# SCH_NFC-TAG-WITH-LED_2024-06-19.net
KiCad netlist of a schematic drawn in EasyEDA
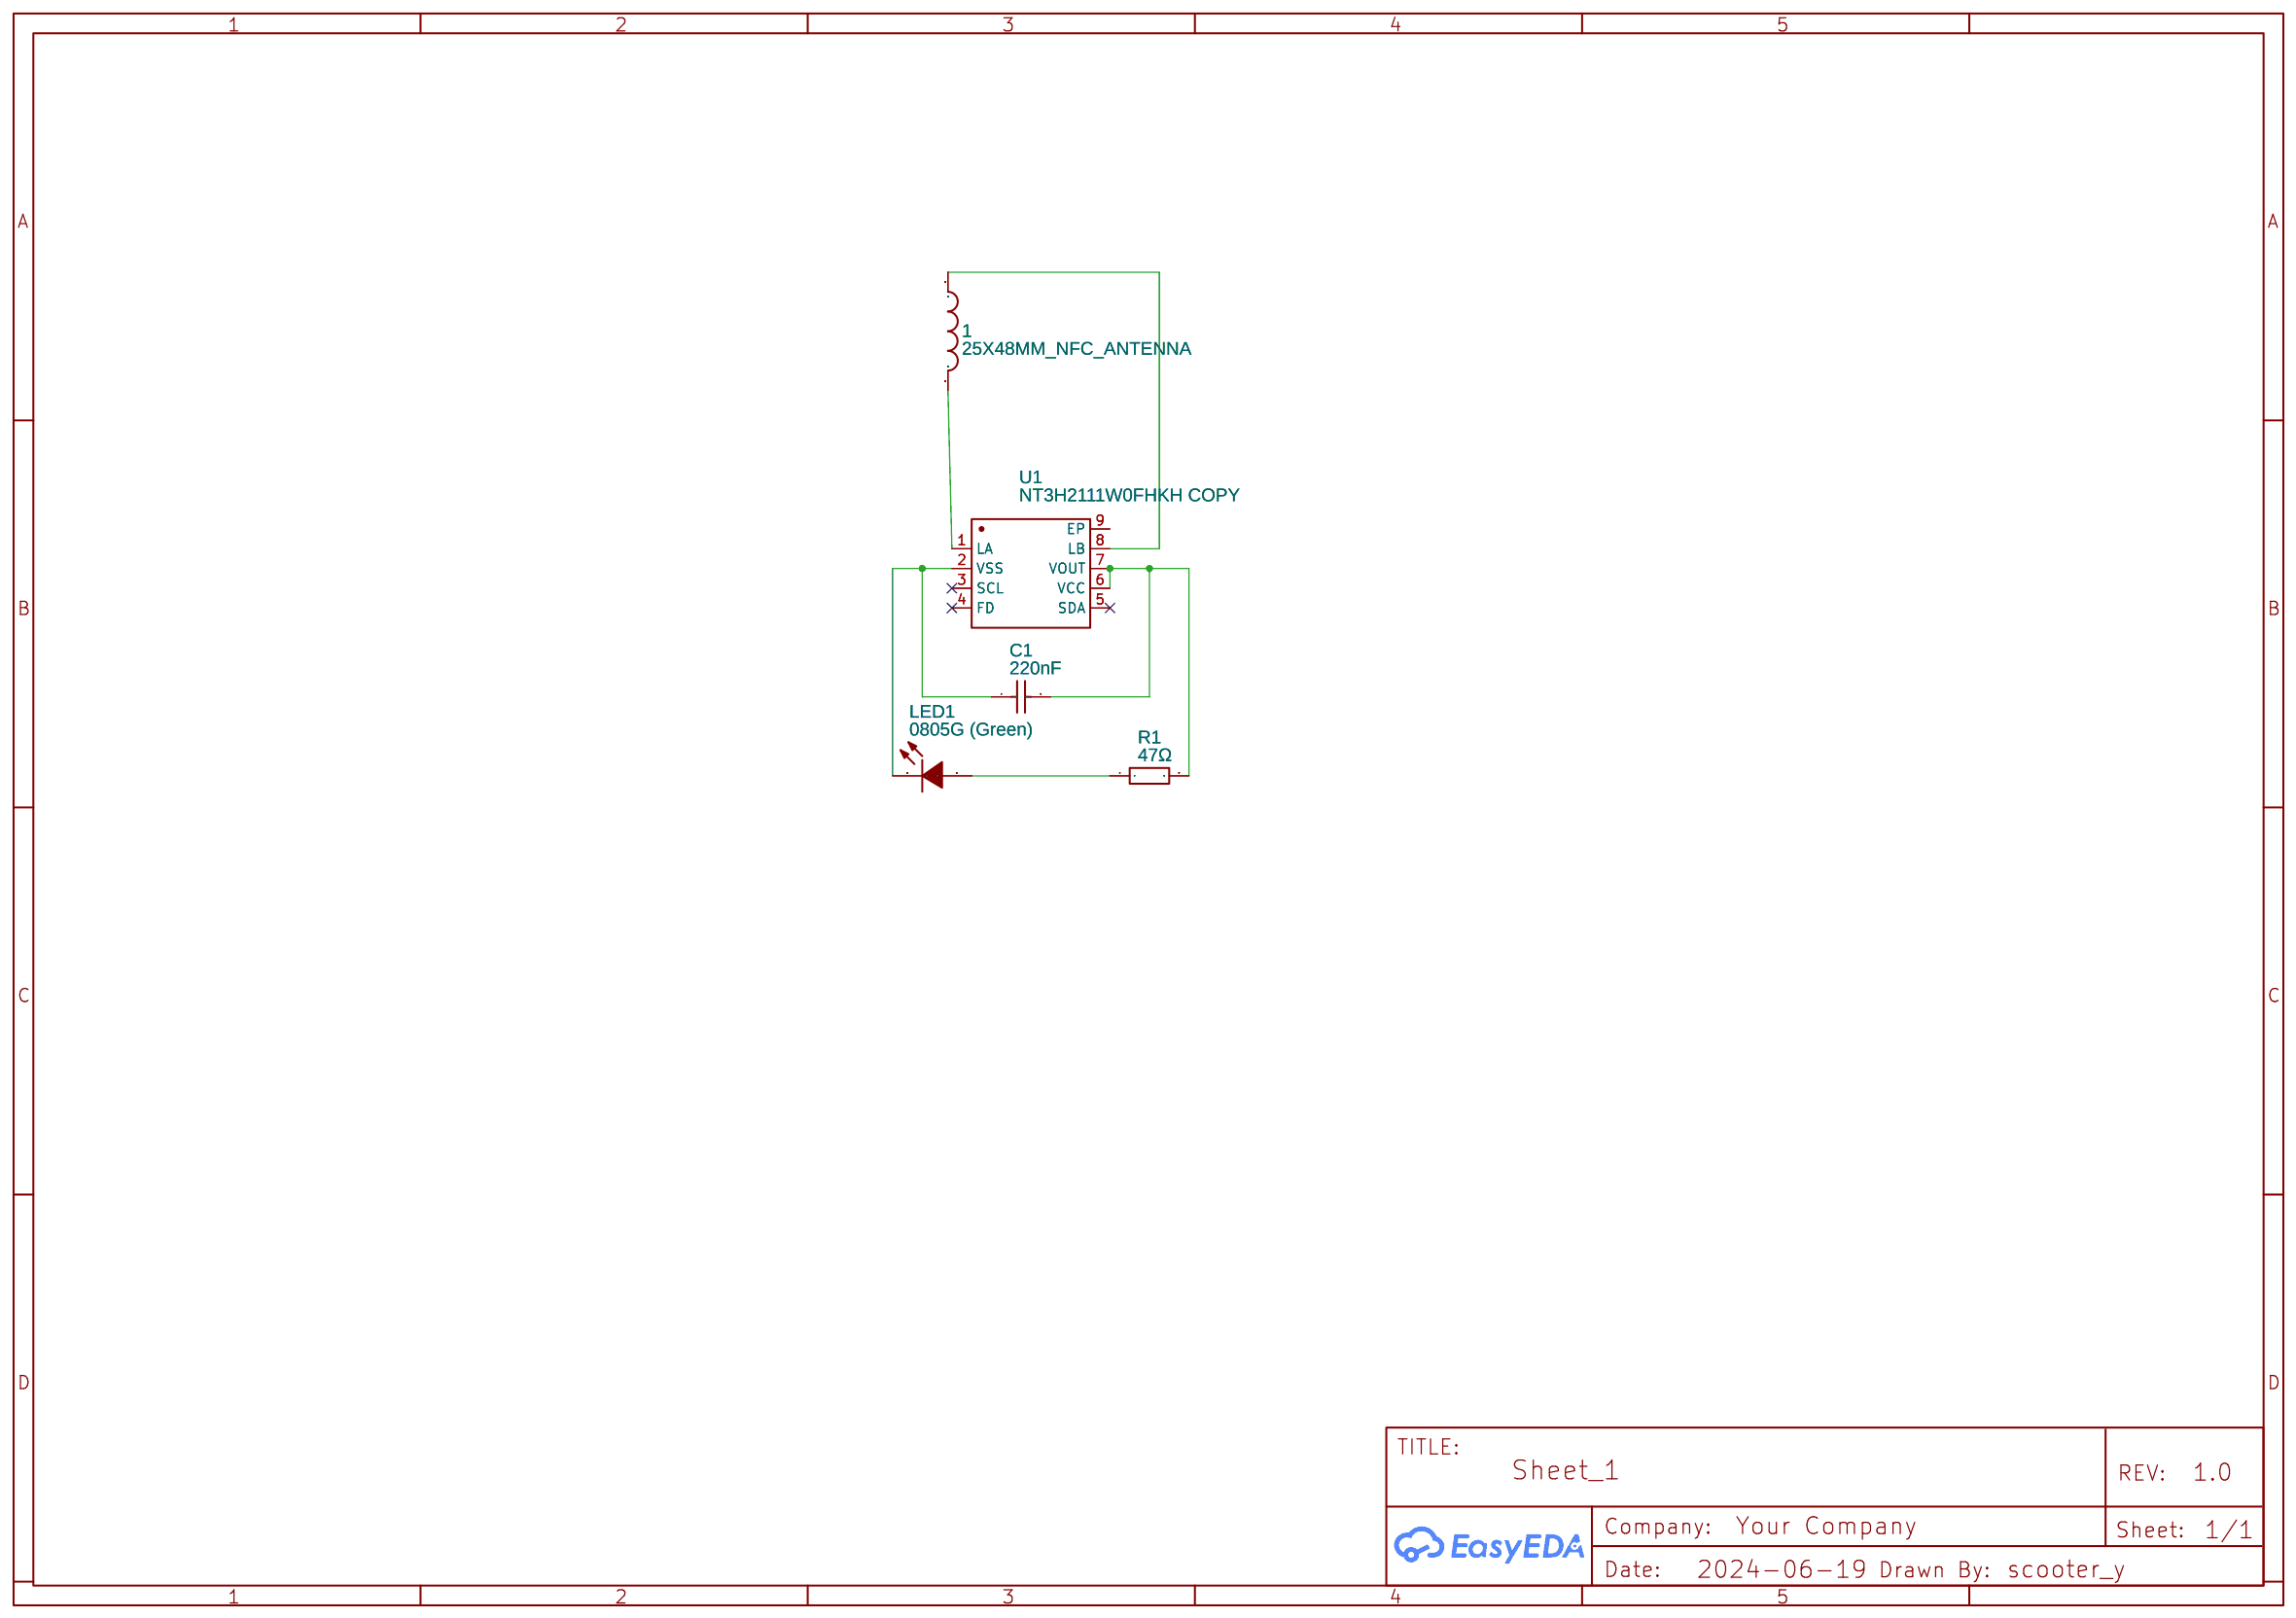
[diagram p0: schematic sheet]

(export (version "E")
  (design (tool "Eeschema 10.0.6"))
  (components
    (comp (ref "1") (value "25X48MM_NFC_ANTENNA") (libsource (lib "") (part "25X48MM_NFC_ANTENNA")))
    (comp (ref "C1")
      (value "220nF")
      (fields
        (field (name "Manufacturer Part") "CL10B224KA8NNNC")
        (field (name "Manufacturer") "SAMSUNG(三星)")
      )
      (libsource (lib "") (part "CL10B224KA8NNNC"))
    )
    (comp (ref "LED1")
      (value "0805G (Green)")
      (fields (field (name "Manufacturer Part") "KT-0805G") (field (name "Manufacturer") "KENTO"))
      (libsource (lib "") (part "0805G (Green)"))
    )
    (comp (ref "R1")
      (value "47Ω")
      (fields
        (field (name "Manufacturer Part") "0603WAF470JT5E")
        (field (name "Manufacturer") "UNI-ROYAL(厚声)")
      )
      (libsource (lib "") (part "0603WAF470JT5E"))
    )
    (comp (ref "U1")
      (value "NT3H2111W0FHKH COPY")
      (fields (field (name "Manufacturer Part") "NT3H2111W0FHKH") (field (name "Manufacturer") "NXP(恩智浦)"))
      (libsource (lib "") (part "NT3H2111W0FHKH COPY"))
    )
  )
  (nets
    (net (code "1") (name "Net-(LED1-A)") (class "Default")
      (node (ref "LED1") (pin "1") (pinfunction "A_1") (pintype "unspecified"))
      (node (ref "R1") (pin "1") (pinfunction "1_1") (pintype "input"))
    )
    (net (code "2") (name "Net-(LED1-K)") (class "Default")
      (node (ref "C1") (pin "1") (pinfunction "1_1") (pintype "input"))
      (node (ref "LED1") (pin "2") (pinfunction "K_2") (pintype "unspecified"))
      (node (ref "U1") (pin "2") (pinfunction "VSS_2") (pintype "unspecified"))
    )
    (net (code "3") (name "Net-(U1-LA)") (class "Default")
      (node (ref "1") (pin "P$2") (pinfunction "P$2_P$2") (pintype "bidirectional"))
      (node (ref "U1") (pin "1") (pinfunction "LA_1") (pintype "unspecified"))
    )
    (net (code "4") (name "Net-(U1-LB)") (class "Default")
      (node (ref "1") (pin "P$1") (pinfunction "P$1_P$1") (pintype "bidirectional"))
      (node (ref "U1") (pin "8") (pinfunction "LB_8") (pintype "unspecified"))
    )
    (net (code "5") (name "Net-(U1-VCC)") (class "Default")
      (node (ref "C1") (pin "2") (pinfunction "2_2") (pintype "input"))
      (node (ref "R1") (pin "2") (pinfunction "2_2") (pintype "input"))
      (node (ref "U1") (pin "6") (pinfunction "VCC_6") (pintype "unspecified"))
      (node (ref "U1") (pin "7") (pinfunction "VOUT_7") (pintype "unspecified"))
    )
    (net (code "6") (name "unconnected-(U1-EP-Pad9)") (class "Default")
      (node (ref "U1") (pin "9") (pinfunction "EP_9") (pintype "unspecified"))
    )
    (net (code "7") (name "unconnected-(U1-FD-Pad4)") (class "Default")
      (node (ref "U1") (pin "4") (pinfunction "FD_4") (pintype "unspecified+no_connect"))
    )
    (net (code "8") (name "unconnected-(U1-SCL-Pad3)") (class "Default")
      (node (ref "U1") (pin "3") (pinfunction "SCL_3") (pintype "unspecified+no_connect"))
    )
    (net (code "9") (name "unconnected-(U1-SDA-Pad5)") (class "Default")
      (node (ref "U1") (pin "5") (pinfunction "SDA_5") (pintype "unspecified+no_connect"))
    )
  )
)
